# APP_UD.net
KiCad netlist of a schematic drawn in EAGLE
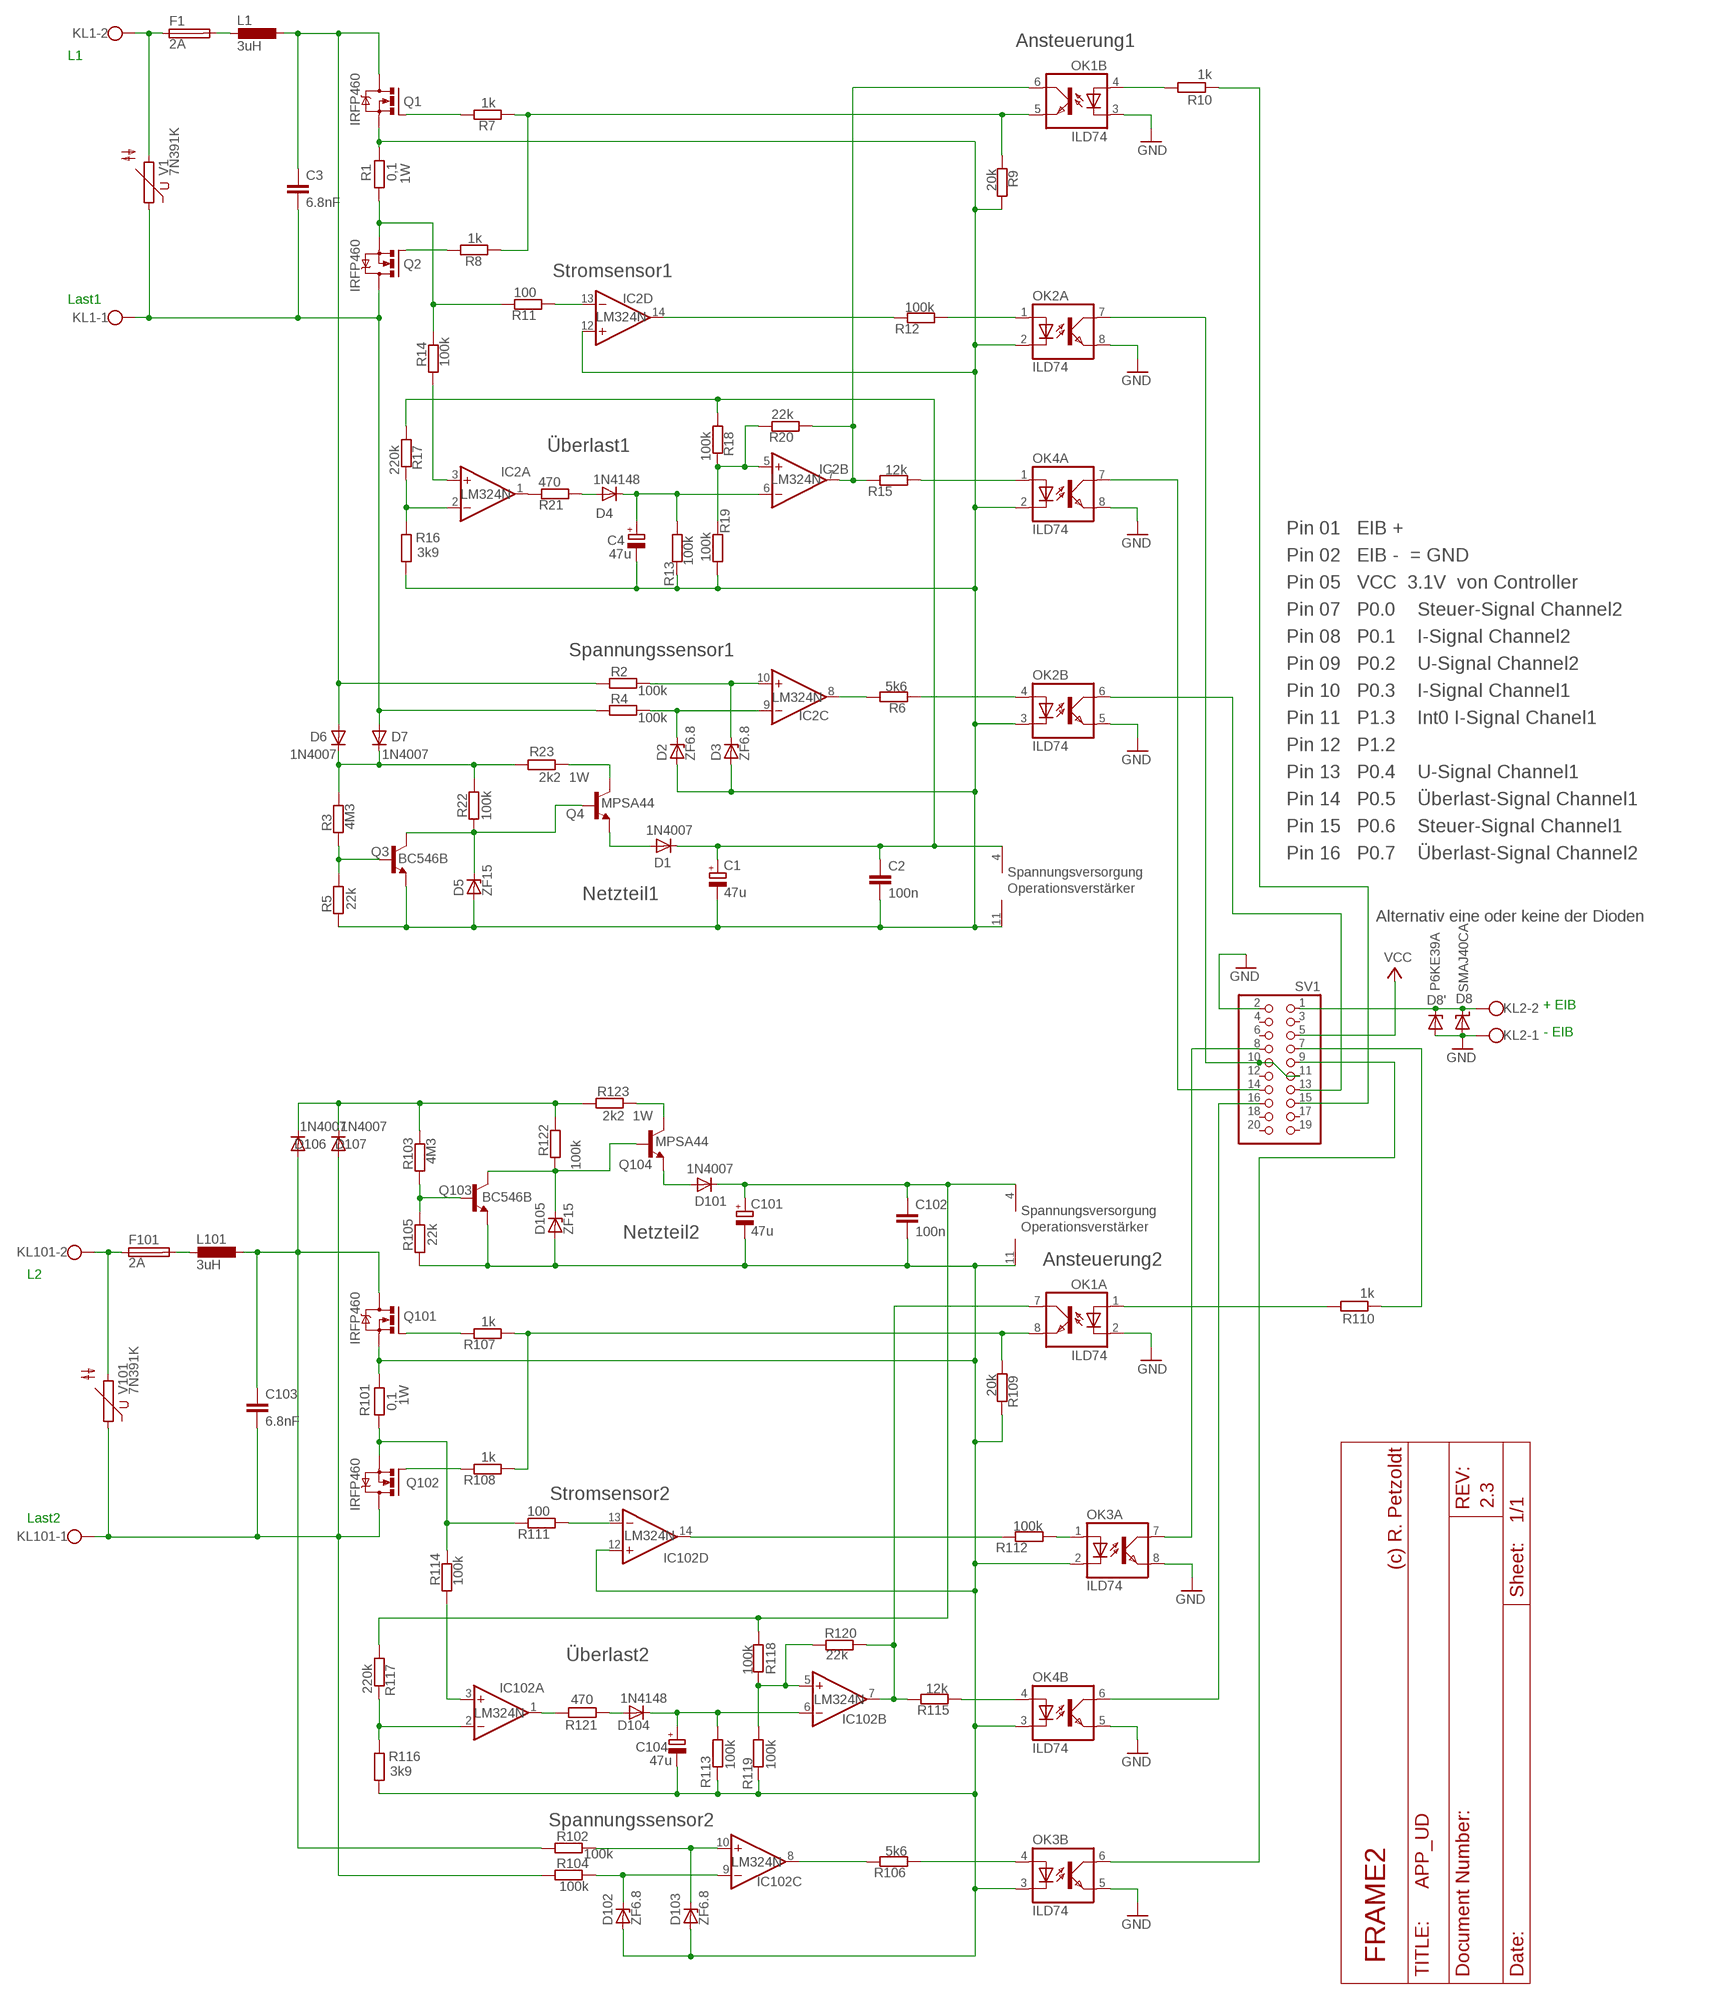
[diagram p0: schematic, sheet 1]

(export (version "E")
  (design (tool "Eeschema 10.0.6"))
  (components
    (comp (ref "C1")
      (value "47u")
      (footprint "eagle-import:E2-5")
      (libsource (lib "eagle-import") (part "CPOL-EUE2-5"))
    )
    (comp (ref "C2")
      (value "100n")
      (footprint "eagle-import:C025-030X050")
      (libsource (lib "eagle-import") (part "C-EU025-030X050"))
    )
    (comp (ref "C3")
      (value "6.8nF")
      (footprint "eagle-import:C050-075X075")
      (libsource (lib "eagle-import") (part "C-EU050-075X075"))
    )
    (comp (ref "C4")
      (value "47u")
      (footprint "eagle-import:E2-5")
      (libsource (lib "eagle-import") (part "CPOL-EUE2-5"))
    )
    (comp (ref "C101")
      (value "47u")
      (footprint "eagle-import:E2-5")
      (libsource (lib "eagle-import") (part "CPOL-EUE2-5"))
    )
    (comp (ref "C102")
      (value "100n")
      (footprint "eagle-import:C025-030X050")
      (libsource (lib "eagle-import") (part "C-EU025-030X050"))
    )
    (comp (ref "C103")
      (value "6.8nF")
      (footprint "eagle-import:C050-075X075")
      (libsource (lib "eagle-import") (part "C-EU050-075X075"))
    )
    (comp (ref "C104")
      (value "47u")
      (footprint "eagle-import:E2-5")
      (libsource (lib "eagle-import") (part "CPOL-EUE2-5"))
    )
    (comp (ref "D1")
      (value "1N4007")
      (footprint "eagle-import:D-7")
      (libsource (lib "eagle-import") (part "1N4148DO35-7S"))
    )
    (comp (ref "D2")
      (value "ZF6.8")
      (footprint "eagle-import:ZDIO-5")
      (libsource (lib "eagle-import") (part "ZENER-DIODEZD-5"))
    )
    (comp (ref "D3")
      (value "ZF6.8")
      (footprint "eagle-import:ZDIO-7.5")
      (libsource (lib "eagle-import") (part "ZENER-DIODEZD-7.5"))
    )
    (comp (ref "D4")
      (value "1N4148")
      (footprint "eagle-import:D-7")
      (libsource (lib "eagle-import") (part "1N4148DO35-7S"))
    )
    (comp (ref "D5")
      (value "ZF15")
      (footprint "eagle-import:ZDIO-7.5")
      (libsource (lib "eagle-import") (part "ZENER-DIODEZD-7.5"))
    )
    (comp (ref "D6")
      (value "1N4007")
      (footprint "eagle-import:D-7.5")
      (libsource (lib "eagle-import") (part "DIODE-D-7.5"))
    )
    (comp (ref "D7")
      (value "1N4007")
      (footprint "eagle-import:D-7.5")
      (libsource (lib "eagle-import") (part "DIODE-D-7.5"))
    )
    (comp (ref "D8")
      (value "SMAJ40CA")
      (footprint "eagle-import:SMBJ")
      (libsource (lib "eagle-import") (part "SUPPRESSOR-SMBJ"))
    )
    (comp (ref "D8'")
      (value "P6KE39A")
      (footprint "eagle-import:ZDIO-7.5")
      (libsource (lib "eagle-import") (part "ZENER-DIODEZD-7.5"))
    )
    (comp (ref "D101")
      (value "1N4007")
      (footprint "eagle-import:D-7")
      (libsource (lib "eagle-import") (part "1N4148DO35-7S"))
    )
    (comp (ref "D102")
      (value "ZF6.8")
      (footprint "eagle-import:ZDIO-5")
      (libsource (lib "eagle-import") (part "ZENER-DIODEZD-5"))
    )
    (comp (ref "D103")
      (value "ZF6.8")
      (footprint "eagle-import:ZDIO-7.5")
      (libsource (lib "eagle-import") (part "ZENER-DIODEZD-7.5"))
    )
    (comp (ref "D104")
      (value "1N4148")
      (footprint "eagle-import:D-7")
      (libsource (lib "eagle-import") (part "1N4148DO35-7S"))
    )
    (comp (ref "D105")
      (value "ZF15")
      (footprint "eagle-import:ZDIO-7.5")
      (libsource (lib "eagle-import") (part "ZENER-DIODEZD-7.5"))
    )
    (comp (ref "D106")
      (value "1N4007")
      (footprint "eagle-import:D-7.5")
      (libsource (lib "eagle-import") (part "DIODE-D-7.5"))
    )
    (comp (ref "D107")
      (value "1N4007")
      (footprint "eagle-import:D-7.5")
      (libsource (lib "eagle-import") (part "DIODE-D-7.5"))
    )
    (comp (ref "F1")
      (value "2A")
      (footprint "eagle-import:TR5")
      (libsource (lib "eagle-import") (part "TR5"))
    )
    (comp (ref "F101")
      (value "2A")
      (footprint "eagle-import:TR5")
      (libsource (lib "eagle-import") (part "TR5"))
    )
    (comp (ref "IC2")
      (value "LM324N")
      (footprint "eagle-import:DIL14")
      (libsource (lib "eagle-import") (part "LM324N"))
    )
    (comp (ref "IC102")
      (value "LM324N")
      (footprint "eagle-import:DIL14")
      (libsource (lib "eagle-import") (part "LM324N"))
    )
    (comp (ref "KL1")
      (value "W237-102")
      (footprint "eagle-import:W237-102")
      (libsource (lib "eagle-import") (part "W237-102"))
    )
    (comp (ref "KL2")
      (value "W237-102")
      (footprint "eagle-import:W237-102")
      (libsource (lib "eagle-import") (part "W237-102"))
    )
    (comp (ref "KL101")
      (value "W237-102")
      (footprint "eagle-import:W237-102")
      (libsource (lib "eagle-import") (part "W237-102"))
    )
    (comp (ref "L1")
      (value "3uH")
      (footprint "eagle-import:0414V")
      (libsource (lib "eagle-import") (part "L-EU414V"))
    )
    (comp (ref "L101")
      (value "3uH")
      (footprint "eagle-import:0414V")
      (libsource (lib "eagle-import") (part "L-EU414V"))
    )
    (comp (ref "OK1")
      (value "ILD74")
      (footprint "eagle-import:DIL08")
      (libsource (lib "eagle-import") (part "ILD2"))
    )
    (comp (ref "OK2")
      (value "ILD74")
      (footprint "eagle-import:DIL08")
      (libsource (lib "eagle-import") (part "ILD2"))
    )
    (comp (ref "OK3")
      (value "ILD74")
      (footprint "eagle-import:DIL08")
      (libsource (lib "eagle-import") (part "ILD2"))
    )
    (comp (ref "OK4")
      (value "ILD74")
      (footprint "eagle-import:DIL08")
      (libsource (lib "eagle-import") (part "ILD2"))
    )
    (comp (ref "Q1")
      (value "IRFP460")
      (footprint "eagle-import:TO247BV")
      (libsource (lib "eagle-import") (part "IRFPC40"))
    )
    (comp (ref "Q2")
      (value "IRFP460")
      (footprint "eagle-import:TO247BV")
      (libsource (lib "eagle-import") (part "IRFPC40"))
    )
    (comp (ref "Q3")
      (value "BC546B")
      (footprint "eagle-import:TO92-EBC")
      (libsource (lib "eagle-import") (part "BC546B"))
    )
    (comp (ref "Q4")
      (value "MPSA44")
      (footprint "eagle-import:TO92-EBC")
      (libsource (lib "eagle-import") (part "-NPN-TO92-EBCMPSA44"))
    )
    (comp (ref "Q101")
      (value "IRFP460")
      (footprint "eagle-import:TO247BV")
      (libsource (lib "eagle-import") (part "IRFPC40"))
    )
    (comp (ref "Q102")
      (value "IRFP460")
      (footprint "eagle-import:TO247BV")
      (libsource (lib "eagle-import") (part "IRFPC40"))
    )
    (comp (ref "Q103")
      (value "BC546B")
      (footprint "eagle-import:TO92-EBC")
      (libsource (lib "eagle-import") (part "BC546B"))
    )
    (comp (ref "Q104")
      (value "MPSA44")
      (footprint "eagle-import:TO92-EBC")
      (libsource (lib "eagle-import") (part "-NPN-TO92-EBCMPSA44"))
    )
    (comp (ref "R1")
      (value "0,1")
      (footprint "eagle-import:0414V")
      (libsource (lib "eagle-import") (part "R-EU_0414/5V"))
    )
    (comp (ref "R2")
      (value "100k")
      (footprint "eagle-import:0204_7")
      (libsource (lib "eagle-import") (part "R-EU_0204/7"))
    )
    (comp (ref "R3")
      (value "4M3")
      (footprint "eagle-import:0204_7")
      (libsource (lib "eagle-import") (part "R-EU_0204/7"))
    )
    (comp (ref "R4")
      (value "100k")
      (footprint "eagle-import:0204_7")
      (libsource (lib "eagle-import") (part "R-EU_0204/7"))
    )
    (comp (ref "R5")
      (value "22k")
      (footprint "eagle-import:0204_7")
      (libsource (lib "eagle-import") (part "R-EU_0204/7"))
    )
    (comp (ref "R6")
      (value "5k6")
      (footprint "eagle-import:0204_7")
      (libsource (lib "eagle-import") (part "R-EU_0204/7"))
    )
    (comp (ref "R7")
      (value "1k")
      (footprint "eagle-import:0204_7")
      (libsource (lib "eagle-import") (part "R-EU_0204/7"))
    )
    (comp (ref "R8")
      (value "1k")
      (footprint "eagle-import:0204_7")
      (libsource (lib "eagle-import") (part "R-EU_0204/7"))
    )
    (comp (ref "R9")
      (value "20k")
      (footprint "eagle-import:0204_7")
      (libsource (lib "eagle-import") (part "R-EU_0204/7"))
    )
    (comp (ref "R10")
      (value "1k")
      (footprint "eagle-import:0204_7")
      (libsource (lib "eagle-import") (part "R-EU_0204/7"))
    )
    (comp (ref "R11")
      (value "100")
      (footprint "eagle-import:0204_7")
      (libsource (lib "eagle-import") (part "R-EU_0204/7"))
    )
    (comp (ref "R12")
      (value "100k")
      (footprint "eagle-import:0204_7")
      (libsource (lib "eagle-import") (part "R-EU_0204/7"))
    )
    (comp (ref "R13")
      (value "100k")
      (footprint "eagle-import:0204_7")
      (libsource (lib "eagle-import") (part "R-EU_0204/7"))
    )
    (comp (ref "R14")
      (value "100k")
      (footprint "eagle-import:0204_7")
      (libsource (lib "eagle-import") (part "R-EU_0204/7"))
    )
    (comp (ref "R15")
      (value "12k")
      (footprint "eagle-import:0204_7")
      (libsource (lib "eagle-import") (part "R-EU_0204/7"))
    )
    (comp (ref "R16")
      (value "3k9")
      (footprint "eagle-import:0204_7")
      (libsource (lib "eagle-import") (part "R-EU_0204/7"))
    )
    (comp (ref "R17")
      (value "220k")
      (footprint "eagle-import:0204_7")
      (libsource (lib "eagle-import") (part "R-EU_0204/7"))
    )
    (comp (ref "R18")
      (value "100k")
      (footprint "eagle-import:0204_7")
      (libsource (lib "eagle-import") (part "R-EU_0204/7"))
    )
    (comp (ref "R19")
      (value "100k")
      (footprint "eagle-import:0204_7")
      (libsource (lib "eagle-import") (part "R-EU_0204/7"))
    )
    (comp (ref "R20")
      (value "22k")
      (footprint "eagle-import:0204_7")
      (libsource (lib "eagle-import") (part "R-EU_0204/7"))
    )
    (comp (ref "R21")
      (value "470")
      (footprint "eagle-import:0204_7")
      (libsource (lib "eagle-import") (part "R-EU_0204/7"))
    )
    (comp (ref "R22")
      (value "100k")
      (footprint "eagle-import:0204_7")
      (libsource (lib "eagle-import") (part "R-EU_0204/7"))
    )
    (comp (ref "R23")
      (value "2k2 1W")
      (footprint "eagle-import:0207_15")
      (libsource (lib "eagle-import") (part "R-EU_0207/15"))
    )
    (comp (ref "R101")
      (value "0,1")
      (footprint "eagle-import:0414V")
      (libsource (lib "eagle-import") (part "R-EU_0414/5V"))
    )
    (comp (ref "R102")
      (value "100k")
      (footprint "eagle-import:0204_7")
      (libsource (lib "eagle-import") (part "R-EU_0204/7"))
    )
    (comp (ref "R103")
      (value "4M3")
      (footprint "eagle-import:0204_7")
      (libsource (lib "eagle-import") (part "R-EU_0204/7"))
    )
    (comp (ref "R104")
      (value "100k")
      (footprint "eagle-import:0204_7")
      (libsource (lib "eagle-import") (part "R-EU_0204/7"))
    )
    (comp (ref "R105")
      (value "22k")
      (footprint "eagle-import:0204_7")
      (libsource (lib "eagle-import") (part "R-EU_0204/7"))
    )
    (comp (ref "R106")
      (value "5k6")
      (footprint "eagle-import:0204_7")
      (libsource (lib "eagle-import") (part "R-EU_0204/7"))
    )
    (comp (ref "R107")
      (value "1k")
      (footprint "eagle-import:0204_7")
      (libsource (lib "eagle-import") (part "R-EU_0204/7"))
    )
    (comp (ref "R108")
      (value "1k")
      (footprint "eagle-import:0204_7")
      (libsource (lib "eagle-import") (part "R-EU_0204/7"))
    )
    (comp (ref "R109")
      (value "20k")
      (footprint "eagle-import:0204_7")
      (libsource (lib "eagle-import") (part "R-EU_0204/7"))
    )
    (comp (ref "R110")
      (value "1k")
      (footprint "eagle-import:0204_7")
      (libsource (lib "eagle-import") (part "R-EU_0204/7"))
    )
    (comp (ref "R111")
      (value "100")
      (footprint "eagle-import:0204_7")
      (libsource (lib "eagle-import") (part "R-EU_0204/7"))
    )
    (comp (ref "R112")
      (value "100k")
      (footprint "eagle-import:0207_15")
      (libsource (lib "eagle-import") (part "R-EU_0207/15"))
    )
    (comp (ref "R113")
      (value "100k")
      (footprint "eagle-import:0204_7")
      (libsource (lib "eagle-import") (part "R-EU_0204/7"))
    )
    (comp (ref "R114")
      (value "100k")
      (footprint "eagle-import:0204_7")
      (libsource (lib "eagle-import") (part "R-EU_0204/7"))
    )
    (comp (ref "R115")
      (value "12k")
      (footprint "eagle-import:0204_7")
      (libsource (lib "eagle-import") (part "R-EU_0204/7"))
    )
    (comp (ref "R116")
      (value "3k9")
      (footprint "eagle-import:0204_7")
      (libsource (lib "eagle-import") (part "R-EU_0204/7"))
    )
    (comp (ref "R117")
      (value "220k")
      (footprint "eagle-import:0204_7")
      (libsource (lib "eagle-import") (part "R-EU_0204/7"))
    )
    (comp (ref "R118")
      (value "100k")
      (footprint "eagle-import:0204_7")
      (libsource (lib "eagle-import") (part "R-EU_0204/7"))
    )
    (comp (ref "R119")
      (value "100k")
      (footprint "eagle-import:0204_7")
      (libsource (lib "eagle-import") (part "R-EU_0204/7"))
    )
    (comp (ref "R120")
      (value "22k")
      (footprint "eagle-import:0204_7")
      (libsource (lib "eagle-import") (part "R-EU_0204/7"))
    )
    (comp (ref "R121")
      (value "470")
      (footprint "eagle-import:0204_7")
      (libsource (lib "eagle-import") (part "R-EU_0204/7"))
    )
    (comp (ref "R122")
      (value "100k")
      (footprint "eagle-import:0204_7")
      (libsource (lib "eagle-import") (part "R-EU_0204/7"))
    )
    (comp (ref "R123")
      (value "2k2 1W")
      (footprint "eagle-import:0207_15")
      (libsource (lib "eagle-import") (part "R-EU_0207/15"))
    )
    (comp (ref "SV1")
      (value "PINHD-2X10")
      (footprint "eagle-import:2X10")
      (libsource (lib "eagle-import") (part "PINHD-2X10"))
    )
    (comp (ref "V1")
      (value "7N391K")
      (footprint "eagle-import:S05K11")
      (libsource (lib "eagle-import") (part "S05K11"))
    )
    (comp (ref "V101")
      (value "7N391K")
      (footprint "eagle-import:S05K11")
      (libsource (lib "eagle-import") (part "S05K11"))
    )
  )
  (nets
    (net (code "1") (name "GND") (class "Default")
      (node (ref "D8") (pin "A") (pinfunction "A_A") (pintype "passive"))
      (node (ref "D8'") (pin "A") (pinfunction "A_A") (pintype "passive"))
      (node (ref "KL2") (pin "1") (pinfunction "KL_1") (pintype "passive"))
      (node (ref "OK1") (pin "2") (pinfunction "C_2") (pintype "passive"))
      (node (ref "OK1") (pin "3") (pinfunction "C_3") (pintype "passive"))
      (node (ref "OK2") (pin "5") (pinfunction "EMIT_5") (pintype "passive"))
      (node (ref "OK2") (pin "8") (pinfunction "EMIT_8") (pintype "passive"))
      (node (ref "OK3") (pin "5") (pinfunction "EMIT_5") (pintype "passive"))
      (node (ref "OK3") (pin "8") (pinfunction "EMIT_8") (pintype "passive"))
      (node (ref "OK4") (pin "5") (pinfunction "EMIT_5") (pintype "passive"))
      (node (ref "OK4") (pin "8") (pinfunction "EMIT_8") (pintype "passive"))
      (node (ref "SV1") (pin "2") (pinfunction "2_2") (pintype "passive"))
    )
    (net (code "2") (name "Net-(C3-Pad1)") (class "Default")
      (node (ref "C3") (pin "1") (pinfunction "1_1") (pintype "passive"))
      (node (ref "D6") (pin "A") (pinfunction "A_A") (pintype "passive"))
      (node (ref "L1") (pin "1") (pinfunction "1_1") (pintype "passive"))
      (node (ref "Q1") (pin "D") (pinfunction "D_D") (pintype "passive"))
      (node (ref "R2") (pin "1") (pinfunction "1_1") (pintype "passive"))
    )
    (net (code "3") (name "Net-(C103-Pad1)") (class "Default")
      (node (ref "C103") (pin "1") (pinfunction "1_1") (pintype "passive"))
      (node (ref "D106") (pin "A") (pinfunction "A_A") (pintype "passive"))
      (node (ref "L101") (pin "1") (pinfunction "1_1") (pintype "passive"))
      (node (ref "Q101") (pin "D") (pinfunction "D_D") (pintype "passive"))
      (node (ref "R102") (pin "1") (pinfunction "1_1") (pintype "passive"))
    )
    (net (code "4") (name "Net-(D1-PadA)") (class "Default")
      (node (ref "D1") (pin "A") (pinfunction "A_A") (pintype "passive"))
      (node (ref "Q4") (pin "E") (pinfunction "E_E") (pintype "passive"))
    )
    (net (code "5") (name "Net-(D4-PadA)") (class "Default")
      (node (ref "D4") (pin "A") (pinfunction "A_A") (pintype "passive"))
      (node (ref "R21") (pin "1") (pinfunction "1_1") (pintype "passive"))
    )
    (net (code "6") (name "Net-(D5-PadC)") (class "Default")
      (node (ref "D5") (pin "C") (pinfunction "C_C") (pintype "passive"))
      (node (ref "Q3") (pin "C") (pinfunction "C_C") (pintype "passive"))
      (node (ref "Q4") (pin "B") (pinfunction "B_B") (pintype "passive"))
      (node (ref "R22") (pin "1") (pinfunction "1_1") (pintype "passive"))
    )
    (net (code "7") (name "Net-(D6-PadC)") (class "Default")
      (node (ref "D6") (pin "C") (pinfunction "C_C") (pintype "passive"))
      (node (ref "D7") (pin "C") (pinfunction "C_C") (pintype "passive"))
      (node (ref "R22") (pin "2") (pinfunction "2_2") (pintype "passive"))
      (node (ref "R23") (pin "1") (pinfunction "1_1") (pintype "passive"))
      (node (ref "R3") (pin "2") (pinfunction "2_2") (pintype "passive"))
    )
    (net (code "8") (name "Net-(D101-PadA)") (class "Default")
      (node (ref "D101") (pin "A") (pinfunction "A_A") (pintype "passive"))
      (node (ref "Q104") (pin "E") (pinfunction "E_E") (pintype "passive"))
    )
    (net (code "9") (name "Net-(D104-PadA)") (class "Default")
      (node (ref "D104") (pin "A") (pinfunction "A_A") (pintype "passive"))
      (node (ref "R121") (pin "1") (pinfunction "1_1") (pintype "passive"))
    )
    (net (code "10") (name "Net-(D105-PadC)") (class "Default")
      (node (ref "D105") (pin "C") (pinfunction "C_C") (pintype "passive"))
      (node (ref "Q103") (pin "C") (pinfunction "C_C") (pintype "passive"))
      (node (ref "Q104") (pin "B") (pinfunction "B_B") (pintype "passive"))
      (node (ref "R122") (pin "1") (pinfunction "1_1") (pintype "passive"))
    )
    (net (code "11") (name "Net-(D106-PadC)") (class "Default")
      (node (ref "D106") (pin "C") (pinfunction "C_C") (pintype "passive"))
      (node (ref "D107") (pin "C") (pinfunction "C_C") (pintype "passive"))
      (node (ref "R103") (pin "2") (pinfunction "2_2") (pintype "passive"))
      (node (ref "R122") (pin "2") (pinfunction "2_2") (pintype "passive"))
      (node (ref "R123") (pin "1") (pinfunction "1_1") (pintype "passive"))
    )
    (net (code "12") (name "Net-(F1-Pad2)") (class "Default")
      (node (ref "F1") (pin "2") (pinfunction "2_2") (pintype "passive"))
      (node (ref "L1") (pin "2") (pinfunction "2_2") (pintype "passive"))
    )
    (net (code "13") (name "Net-(F101-Pad2)") (class "Default")
      (node (ref "F101") (pin "2") (pinfunction "2_2") (pintype "passive"))
      (node (ref "L101") (pin "2") (pinfunction "2_2") (pintype "passive"))
    )
    (net (code "14") (name "Net-(IC2A-+IN)") (class "Default")
      (node (ref "IC2") (pin "3") (pinfunction "+IN_3") (pintype "input"))
      (node (ref "R14") (pin "1") (pinfunction "1_1") (pintype "passive"))
    )
    (net (code "15") (name "Net-(IC2A--IN)") (class "Default")
      (node (ref "IC2") (pin "2") (pinfunction "-IN_2") (pintype "input"))
      (node (ref "R16") (pin "1") (pinfunction "1_1") (pintype "passive"))
      (node (ref "R17") (pin "2") (pinfunction "2_2") (pintype "passive"))
    )
    (net (code "16") (name "Net-(IC2A-OUT)") (class "Default")
      (node (ref "IC2") (pin "1") (pinfunction "OUT_1") (pintype "output"))
      (node (ref "R21") (pin "2") (pinfunction "2_2") (pintype "passive"))
    )
    (net (code "17") (name "Net-(IC2B-+IN)") (class "Default")
      (node (ref "IC2") (pin "5") (pinfunction "+IN_5") (pintype "input"))
      (node (ref "R18") (pin "2") (pinfunction "2_2") (pintype "passive"))
      (node (ref "R19") (pin "2") (pinfunction "2_2") (pintype "passive"))
      (node (ref "R20") (pin "2") (pinfunction "2_2") (pintype "passive"))
    )
    (net (code "18") (name "Net-(IC2B--IN)") (class "Default")
      (node (ref "C4") (pin "+") (pinfunction "+_+") (pintype "passive"))
      (node (ref "D4") (pin "C") (pinfunction "C_C") (pintype "passive"))
      (node (ref "IC2") (pin "6") (pinfunction "-IN_6") (pintype "input"))
      (node (ref "R13") (pin "1") (pinfunction "1_1") (pintype "passive"))
    )
    (net (code "19") (name "Net-(IC2B-OUT)") (class "Default")
      (node (ref "IC2") (pin "7") (pinfunction "OUT_7") (pintype "output"))
      (node (ref "OK1") (pin "6") (pinfunction "COL_6") (pintype "passive"))
      (node (ref "R15") (pin "2") (pinfunction "2_2") (pintype "passive"))
      (node (ref "R20") (pin "1") (pinfunction "1_1") (pintype "passive"))
    )
    (net (code "20") (name "Net-(IC2C-+IN)") (class "Default")
      (node (ref "D3") (pin "C") (pinfunction "C_C") (pintype "passive"))
      (node (ref "IC2") (pin "10") (pinfunction "+IN_10") (pintype "input"))
      (node (ref "R2") (pin "2") (pinfunction "2_2") (pintype "passive"))
    )
    (net (code "21") (name "Net-(IC2C--IN)") (class "Default")
      (node (ref "D2") (pin "C") (pinfunction "C_C") (pintype "passive"))
      (node (ref "IC2") (pin "9") (pinfunction "-IN_9") (pintype "input"))
      (node (ref "R4") (pin "2") (pinfunction "2_2") (pintype "passive"))
    )
    (net (code "22") (name "Net-(IC2C-OUT)") (class "Default")
      (node (ref "IC2") (pin "8") (pinfunction "OUT_8") (pintype "output"))
      (node (ref "R6") (pin "2") (pinfunction "2_2") (pintype "passive"))
    )
    (net (code "23") (name "Net-(IC2D-+IN)") (class "Default")
      (node (ref "C1") (pin "-") (pinfunction "-_-") (pintype "passive"))
      (node (ref "C2") (pin "2") (pinfunction "2_2") (pintype "passive"))
      (node (ref "C4") (pin "-") (pinfunction "-_-") (pintype "passive"))
      (node (ref "D2") (pin "A") (pinfunction "A_A") (pintype "passive"))
      (node (ref "D3") (pin "A") (pinfunction "A_A") (pintype "passive"))
      (node (ref "D5") (pin "A") (pinfunction "A_A") (pintype "passive"))
      (node (ref "IC2") (pin "11") (pinfunction "V-_11") (pintype "power_in"))
      (node (ref "IC2") (pin "12") (pinfunction "+IN_12") (pintype "input"))
      (node (ref "OK2") (pin "2") (pinfunction "C_2") (pintype "passive"))
      (node (ref "OK2") (pin "3") (pinfunction "C_3") (pintype "passive"))
      (node (ref "OK4") (pin "2") (pinfunction "C_2") (pintype "passive"))
      (node (ref "Q1") (pin "S") (pinfunction "S_S") (pintype "passive"))
      (node (ref "Q3") (pin "E") (pinfunction "E_E") (pintype "passive"))
      (node (ref "R1") (pin "2") (pinfunction "2_2") (pintype "passive"))
      (node (ref "R13") (pin "2") (pinfunction "2_2") (pintype "passive"))
      (node (ref "R16") (pin "2") (pinfunction "2_2") (pintype "passive"))
      (node (ref "R19") (pin "1") (pinfunction "1_1") (pintype "passive"))
      (node (ref "R5") (pin "1") (pinfunction "1_1") (pintype "passive"))
      (node (ref "R9") (pin "2") (pinfunction "2_2") (pintype "passive"))
    )
    (net (code "24") (name "Net-(IC2D--IN)") (class "Default")
      (node (ref "IC2") (pin "13") (pinfunction "-IN_13") (pintype "input"))
      (node (ref "R11") (pin "1") (pinfunction "1_1") (pintype "passive"))
    )
    (net (code "25") (name "Net-(IC2D-OUT)") (class "Default")
      (node (ref "IC2") (pin "14") (pinfunction "OUT_14") (pintype "output"))
      (node (ref "R12") (pin "2") (pinfunction "2_2") (pintype "passive"))
    )
    (net (code "26") (name "Net-(IC2E-V+)") (class "Default")
      (node (ref "C1") (pin "+") (pinfunction "+_+") (pintype "passive"))
      (node (ref "C2") (pin "1") (pinfunction "1_1") (pintype "passive"))
      (node (ref "D1") (pin "C") (pinfunction "C_C") (pintype "passive"))
      (node (ref "IC2") (pin "4") (pinfunction "V+_4") (pintype "power_in"))
      (node (ref "R17") (pin "1") (pinfunction "1_1") (pintype "passive"))
      (node (ref "R18") (pin "1") (pinfunction "1_1") (pintype "passive"))
    )
    (net (code "27") (name "Net-(IC102A-+IN)") (class "Default")
      (node (ref "IC102") (pin "3") (pinfunction "+IN_3") (pintype "input"))
      (node (ref "R114") (pin "1") (pinfunction "1_1") (pintype "passive"))
    )
    (net (code "28") (name "Net-(IC102A--IN)") (class "Default")
      (node (ref "IC102") (pin "2") (pinfunction "-IN_2") (pintype "input"))
      (node (ref "R116") (pin "1") (pinfunction "1_1") (pintype "passive"))
      (node (ref "R117") (pin "2") (pinfunction "2_2") (pintype "passive"))
    )
    (net (code "29") (name "Net-(IC102A-OUT)") (class "Default")
      (node (ref "IC102") (pin "1") (pinfunction "OUT_1") (pintype "output"))
      (node (ref "R121") (pin "2") (pinfunction "2_2") (pintype "passive"))
    )
    (net (code "30") (name "Net-(IC102B-+IN)") (class "Default")
      (node (ref "IC102") (pin "5") (pinfunction "+IN_5") (pintype "input"))
      (node (ref "R118") (pin "2") (pinfunction "2_2") (pintype "passive"))
      (node (ref "R119") (pin "1") (pinfunction "1_1") (pintype "passive"))
      (node (ref "R120") (pin "1") (pinfunction "1_1") (pintype "passive"))
    )
    (net (code "31") (name "Net-(IC102B--IN)") (class "Default")
      (node (ref "C104") (pin "+") (pinfunction "+_+") (pintype "passive"))
      (node (ref "D104") (pin "C") (pinfunction "C_C") (pintype "passive"))
      (node (ref "IC102") (pin "6") (pinfunction "-IN_6") (pintype "input"))
      (node (ref "R113") (pin "1") (pinfunction "1_1") (pintype "passive"))
    )
    (net (code "32") (name "Net-(IC102B-OUT)") (class "Default")
      (node (ref "IC102") (pin "7") (pinfunction "OUT_7") (pintype "output"))
      (node (ref "OK1") (pin "7") (pinfunction "COL_7") (pintype "passive"))
      (node (ref "R115") (pin "2") (pinfunction "2_2") (pintype "passive"))
      (node (ref "R120") (pin "2") (pinfunction "2_2") (pintype "passive"))
    )
    (net (code "33") (name "Net-(IC102C-+IN)") (class "Default")
      (node (ref "D103") (pin "C") (pinfunction "C_C") (pintype "passive"))
      (node (ref "IC102") (pin "10") (pinfunction "+IN_10") (pintype "input"))
      (node (ref "R102") (pin "2") (pinfunction "2_2") (pintype "passive"))
    )
    (net (code "34") (name "Net-(IC102C--IN)") (class "Default")
      (node (ref "D102") (pin "C") (pinfunction "C_C") (pintype "passive"))
      (node (ref "IC102") (pin "9") (pinfunction "-IN_9") (pintype "input"))
      (node (ref "R104") (pin "2") (pinfunction "2_2") (pintype "passive"))
    )
    (net (code "35") (name "Net-(IC102C-OUT)") (class "Default")
      (node (ref "IC102") (pin "8") (pinfunction "OUT_8") (pintype "output"))
      (node (ref "R106") (pin "2") (pinfunction "2_2") (pintype "passive"))
    )
    (net (code "36") (name "Net-(IC102D-+IN)") (class "Default")
      (node (ref "C101") (pin "-") (pinfunction "-_-") (pintype "passive"))
      (node (ref "C102") (pin "2") (pinfunction "2_2") (pintype "passive"))
      (node (ref "C104") (pin "-") (pinfunction "-_-") (pintype "passive"))
      (node (ref "D102") (pin "A") (pinfunction "A_A") (pintype "passive"))
      (node (ref "D103") (pin "A") (pinfunction "A_A") (pintype "passive"))
      (node (ref "D105") (pin "A") (pinfunction "A_A") (pintype "passive"))
      (node (ref "IC102") (pin "11") (pinfunction "V-_11") (pintype "power_in"))
      (node (ref "IC102") (pin "12") (pinfunction "+IN_12") (pintype "input"))
      (node (ref "OK3") (pin "2") (pinfunction "C_2") (pintype "passive"))
      (node (ref "OK3") (pin "3") (pinfunction "C_3") (pintype "passive"))
      (node (ref "OK4") (pin "3") (pinfunction "C_3") (pintype "passive"))
      (node (ref "Q101") (pin "S") (pinfunction "S_S") (pintype "passive"))
      (node (ref "Q103") (pin "E") (pinfunction "E_E") (pintype "passive"))
      (node (ref "R101") (pin "2") (pinfunction "2_2") (pintype "passive"))
      (node (ref "R105") (pin "1") (pinfunction "1_1") (pintype "passive"))
      (node (ref "R109") (pin "2") (pinfunction "2_2") (pintype "passive"))
      (node (ref "R113") (pin "2") (pinfunction "2_2") (pintype "passive"))
      (node (ref "R116") (pin "2") (pinfunction "2_2") (pintype "passive"))
      (node (ref "R119") (pin "2") (pinfunction "2_2") (pintype "passive"))
    )
    (net (code "37") (name "Net-(IC102D--IN)") (class "Default")
      (node (ref "IC102") (pin "13") (pinfunction "-IN_13") (pintype "input"))
      (node (ref "R111") (pin "1") (pinfunction "1_1") (pintype "passive"))
    )
    (net (code "38") (name "Net-(IC102D-OUT)") (class "Default")
      (node (ref "IC102") (pin "14") (pinfunction "OUT_14") (pintype "output"))
      (node (ref "R112") (pin "2") (pinfunction "2_2") (pintype "passive"))
    )
    (net (code "39") (name "Net-(IC102E-V+)") (class "Default")
      (node (ref "C101") (pin "+") (pinfunction "+_+") (pintype "passive"))
      (node (ref "C102") (pin "1") (pinfunction "1_1") (pintype "passive"))
      (node (ref "D101") (pin "C") (pinfunction "C_C") (pintype "passive"))
      (node (ref "IC102") (pin "4") (pinfunction "V+_4") (pintype "power_in"))
      (node (ref "R117") (pin "1") (pinfunction "1_1") (pintype "passive"))
      (node (ref "R118") (pin "1") (pinfunction "1_1") (pintype "passive"))
    )
    (net (code "40") (name "Net-(KL1A-KL)") (class "Default")
      (node (ref "C3") (pin "2") (pinfunction "2_2") (pintype "passive"))
      (node (ref "D7") (pin "A") (pinfunction "A_A") (pintype "passive"))
      (node (ref "KL1") (pin "1") (pinfunction "KL_1") (pintype "passive"))
      (node (ref "Q2") (pin "D") (pinfunction "D_D") (pintype "passive"))
      (node (ref "R4") (pin "1") (pinfunction "1_1") (pintype "passive"))
      (node (ref "V1") (pin "1") (pinfunction "1_1") (pintype "passive"))
    )
    (net (code "41") (name "Net-(KL1B-KL)") (class "Default")
      (node (ref "F1") (pin "1") (pinfunction "1_1") (pintype "passive"))
      (node (ref "KL1") (pin "2") (pinfunction "KL_2") (pintype "passive"))
      (node (ref "V1") (pin "2") (pinfunction "2_2") (pintype "passive"))
    )
    (net (code "42") (name "Net-(KL2B-KL)") (class "Default")
      (node (ref "D8") (pin "C") (pinfunction "C_C") (pintype "passive"))
      (node (ref "D8'") (pin "C") (pinfunction "C_C") (pintype "passive"))
      (node (ref "KL2") (pin "2") (pinfunction "KL_2") (pintype "passive"))
      (node (ref "SV1") (pin "1") (pinfunction "1_1") (pintype "passive"))
    )
    (net (code "43") (name "Net-(KL101A-KL)") (class "Default")
      (node (ref "C103") (pin "2") (pinfunction "2_2") (pintype "passive"))
      (node (ref "D107") (pin "A") (pinfunction "A_A") (pintype "passive"))
      (node (ref "KL101") (pin "1") (pinfunction "KL_1") (pintype "passive"))
      (node (ref "Q102") (pin "D") (pinfunction "D_D") (pintype "passive"))
      (node (ref "R104") (pin "1") (pinfunction "1_1") (pintype "passive"))
      (node (ref "V101") (pin "1") (pinfunction "1_1") (pintype "passive"))
    )
    (net (code "44") (name "Net-(KL101B-KL)") (class "Default")
      (node (ref "F101") (pin "1") (pinfunction "1_1") (pintype "passive"))
      (node (ref "KL101") (pin "2") (pinfunction "KL_2") (pintype "passive"))
      (node (ref "V101") (pin "2") (pinfunction "2_2") (pintype "passive"))
    )
    (net (code "45") (name "Net-(OK1A-A)") (class "Default")
      (node (ref "OK1") (pin "1") (pinfunction "A_1") (pintype "passive"))
      (node (ref "R110") (pin "2") (pinfunction "2_2") (pintype "passive"))
    )
    (net (code "46") (name "Net-(OK1A-EMIT)") (class "Default")
      (node (ref "OK1") (pin "8") (pinfunction "EMIT_8") (pintype "passive"))
      (node (ref "R107") (pin "1") (pinfunction "1_1") (pintype "passive"))
      (node (ref "R108") (pin "1") (pinfunction "1_1") (pintype "passive"))
      (node (ref "R109") (pin "1") (pinfunction "1_1") (pintype "passive"))
    )
    (net (code "47") (name "Net-(OK1B-A)") (class "Default")
      (node (ref "OK1") (pin "4") (pinfunction "A_4") (pintype "passive"))
      (node (ref "R10") (pin "2") (pinfunction "2_2") (pintype "passive"))
    )
    (net (code "48") (name "Net-(OK1B-EMIT)") (class "Default")
      (node (ref "OK1") (pin "5") (pinfunction "EMIT_5") (pintype "passive"))
      (node (ref "R7") (pin "1") (pinfunction "1_1") (pintype "passive"))
      (node (ref "R8") (pin "1") (pinfunction "1_1") (pintype "passive"))
      (node (ref "R9") (pin "1") (pinfunction "1_1") (pintype "passive"))
    )
    (net (code "49") (name "Net-(OK2A-A)") (class "Default")
      (node (ref "OK2") (pin "1") (pinfunction "A_1") (pintype "passive"))
      (node (ref "R12") (pin "1") (pinfunction "1_1") (pintype "passive"))
    )
    (net (code "50") (name "Net-(OK2A-COL)") (class "Default")
      (node (ref "OK2") (pin "7") (pinfunction "COL_7") (pintype "passive"))
      (node (ref "SV1") (pin "10") (pinfunction "10_10") (pintype "passive"))
      (node (ref "SV1") (pin "11") (pinfunction "11_11") (pintype "passive"))
    )
    (net (code "51") (name "Net-(OK2B-A)") (class "Default")
      (node (ref "OK2") (pin "4") (pinfunction "A_4") (pintype "passive"))
      (node (ref "R6") (pin "1") (pinfunction "1_1") (pintype "passive"))
    )
    (net (code "52") (name "Net-(OK2B-COL)") (class "Default")
      (node (ref "OK2") (pin "6") (pinfunction "COL_6") (pintype "passive"))
      (node (ref "SV1") (pin "13") (pinfunction "13_13") (pintype "passive"))
    )
    (net (code "53") (name "Net-(OK3A-A)") (class "Default")
      (node (ref "OK3") (pin "1") (pinfunction "A_1") (pintype "passive"))
      (node (ref "R112") (pin "1") (pinfunction "1_1") (pintype "passive"))
    )
    (net (code "54") (name "Net-(OK3A-COL)") (class "Default")
      (node (ref "OK3") (pin "7") (pinfunction "COL_7") (pintype "passive"))
      (node (ref "SV1") (pin "8") (pinfunction "8_8") (pintype "passive"))
    )
    (net (code "55") (name "Net-(OK3B-A)") (class "Default")
      (node (ref "OK3") (pin "4") (pinfunction "A_4") (pintype "passive"))
      (node (ref "R106") (pin "1") (pinfunction "1_1") (pintype "passive"))
    )
    (net (code "56") (name "Net-(OK3B-COL)") (class "Default")
      (node (ref "OK3") (pin "6") (pinfunction "COL_6") (pintype "passive"))
      (node (ref "SV1") (pin "9") (pinfunction "9_9") (pintype "passive"))
    )
    (net (code "57") (name "Net-(OK4A-A)") (class "Default")
      (node (ref "OK4") (pin "1") (pinfunction "A_1") (pintype "passive"))
      (node (ref "R15") (pin "1") (pinfunction "1_1") (pintype "passive"))
    )
    (net (code "58") (name "Net-(OK4A-COL)") (class "Default")
      (node (ref "OK4") (pin "7") (pinfunction "COL_7") (pintype "passive"))
      (node (ref "SV1") (pin "14") (pinfunction "14_14") (pintype "passive"))
    )
    (net (code "59") (name "Net-(OK4B-A)") (class "Default")
      (node (ref "OK4") (pin "4") (pinfunction "A_4") (pintype "passive"))
      (node (ref "R115") (pin "1") (pinfunction "1_1") (pintype "passive"))
    )
    (net (code "60") (name "Net-(OK4B-COL)") (class "Default")
      (node (ref "OK4") (pin "6") (pinfunction "COL_6") (pintype "passive"))
      (node (ref "SV1") (pin "16") (pinfunction "16_16") (pintype "passive"))
    )
    (net (code "61") (name "Net-(Q1-PadG)") (class "Default")
      (node (ref "Q1") (pin "G") (pinfunction "G_G") (pintype "passive"))
      (node (ref "R7") (pin "2") (pinfunction "2_2") (pintype "passive"))
    )
    (net (code "62") (name "Net-(Q2-PadG)") (class "Default")
      (node (ref "Q2") (pin "G") (pinfunction "G_G") (pintype "passive"))
      (node (ref "R8") (pin "2") (pinfunction "2_2") (pintype "passive"))
    )
    (net (code "63") (name "Net-(Q2-PadS)") (class "Default")
      (node (ref "Q2") (pin "S") (pinfunction "S_S") (pintype "passive"))
      (node (ref "R1") (pin "1") (pinfunction "1_1") (pintype "passive"))
      (node (ref "R11") (pin "2") (pinfunction "2_2") (pintype "passive"))
      (node (ref "R14") (pin "2") (pinfunction "2_2") (pintype "passive"))
    )
    (net (code "64") (name "Net-(Q3-PadB)") (class "Default")
      (node (ref "Q3") (pin "B") (pinfunction "B_B") (pintype "passive"))
      (node (ref "R3") (pin "1") (pinfunction "1_1") (pintype "passive"))
      (node (ref "R5") (pin "2") (pinfunction "2_2") (pintype "passive"))
    )
    (net (code "65") (name "Net-(Q4-PadC)") (class "Default")
      (node (ref "Q4") (pin "C") (pinfunction "C_C") (pintype "passive"))
      (node (ref "R23") (pin "2") (pinfunction "2_2") (pintype "passive"))
    )
    (net (code "66") (name "Net-(Q101-PadG)") (class "Default")
      (node (ref "Q101") (pin "G") (pinfunction "G_G") (pintype "passive"))
      (node (ref "R107") (pin "2") (pinfunction "2_2") (pintype "passive"))
    )
    (net (code "67") (name "Net-(Q102-PadG)") (class "Default")
      (node (ref "Q102") (pin "G") (pinfunction "G_G") (pintype "passive"))
      (node (ref "R108") (pin "2") (pinfunction "2_2") (pintype "passive"))
    )
    (net (code "68") (name "Net-(Q102-PadS)") (class "Default")
      (node (ref "Q102") (pin "S") (pinfunction "S_S") (pintype "passive"))
      (node (ref "R101") (pin "1") (pinfunction "1_1") (pintype "passive"))
      (node (ref "R111") (pin "2") (pinfunction "2_2") (pintype "passive"))
      (node (ref "R114") (pin "2") (pinfunction "2_2") (pintype "passive"))
    )
    (net (code "69") (name "Net-(Q103-PadB)") (class "Default")
      (node (ref "Q103") (pin "B") (pinfunction "B_B") (pintype "passive"))
      (node (ref "R103") (pin "1") (pinfunction "1_1") (pintype "passive"))
      (node (ref "R105") (pin "2") (pinfunction "2_2") (pintype "passive"))
    )
    (net (code "70") (name "Net-(Q104-PadC)") (class "Default")
      (node (ref "Q104") (pin "C") (pinfunction "C_C") (pintype "passive"))
      (node (ref "R123") (pin "2") (pinfunction "2_2") (pintype "passive"))
    )
    (net (code "71") (name "Net-(R10-Pad1)") (class "Default")
      (node (ref "R10") (pin "1") (pinfunction "1_1") (pintype "passive"))
      (node (ref "SV1") (pin "15") (pinfunction "15_15") (pintype "passive"))
    )
    (net (code "72") (name "Net-(R110-Pad1)") (class "Default")
      (node (ref "R110") (pin "1") (pinfunction "1_1") (pintype "passive"))
      (node (ref "SV1") (pin "7") (pinfunction "7_7") (pintype "passive"))
    )
    (net (code "73") (name "VCC") (class "Default")
      (node (ref "SV1") (pin "5") (pinfunction "5_5") (pintype "passive"))
    )
    (net (code "74") (name "unconnected-(SV1-Pad3)") (class "Default")
      (node (ref "SV1") (pin "3") (pinfunction "3_3") (pintype "passive"))
    )
    (net (code "75") (name "unconnected-(SV1-Pad4)") (class "Default")
      (node (ref "SV1") (pin "4") (pinfunction "4_4") (pintype "passive"))
    )
    (net (code "76") (name "unconnected-(SV1-Pad6)") (class "Default")
      (node (ref "SV1") (pin "6") (pinfunction "6_6") (pintype "passive"))
    )
    (net (code "77") (name "unconnected-(SV1-Pad12)") (class "Default")
      (node (ref "SV1") (pin "12") (pinfunction "12_12") (pintype "passive"))
    )
    (net (code "78") (name "unconnected-(SV1-Pad17)") (class "Default")
      (node (ref "SV1") (pin "17") (pinfunction "17_17") (pintype "passive"))
    )
    (net (code "79") (name "unconnected-(SV1-Pad18)") (class "Default")
      (node (ref "SV1") (pin "18") (pinfunction "18_18") (pintype "passive"))
    )
    (net (code "80") (name "unconnected-(SV1-Pad19)") (class "Default")
      (node (ref "SV1") (pin "19") (pinfunction "19_19") (pintype "passive"))
    )
    (net (code "81") (name "unconnected-(SV1-Pad20)") (class "Default")
      (node (ref "SV1") (pin "20") (pinfunction "20_20") (pintype "passive"))
    )
  )
)
